# S603D.net
KiCad netlist of a schematic drawn in EAGLE
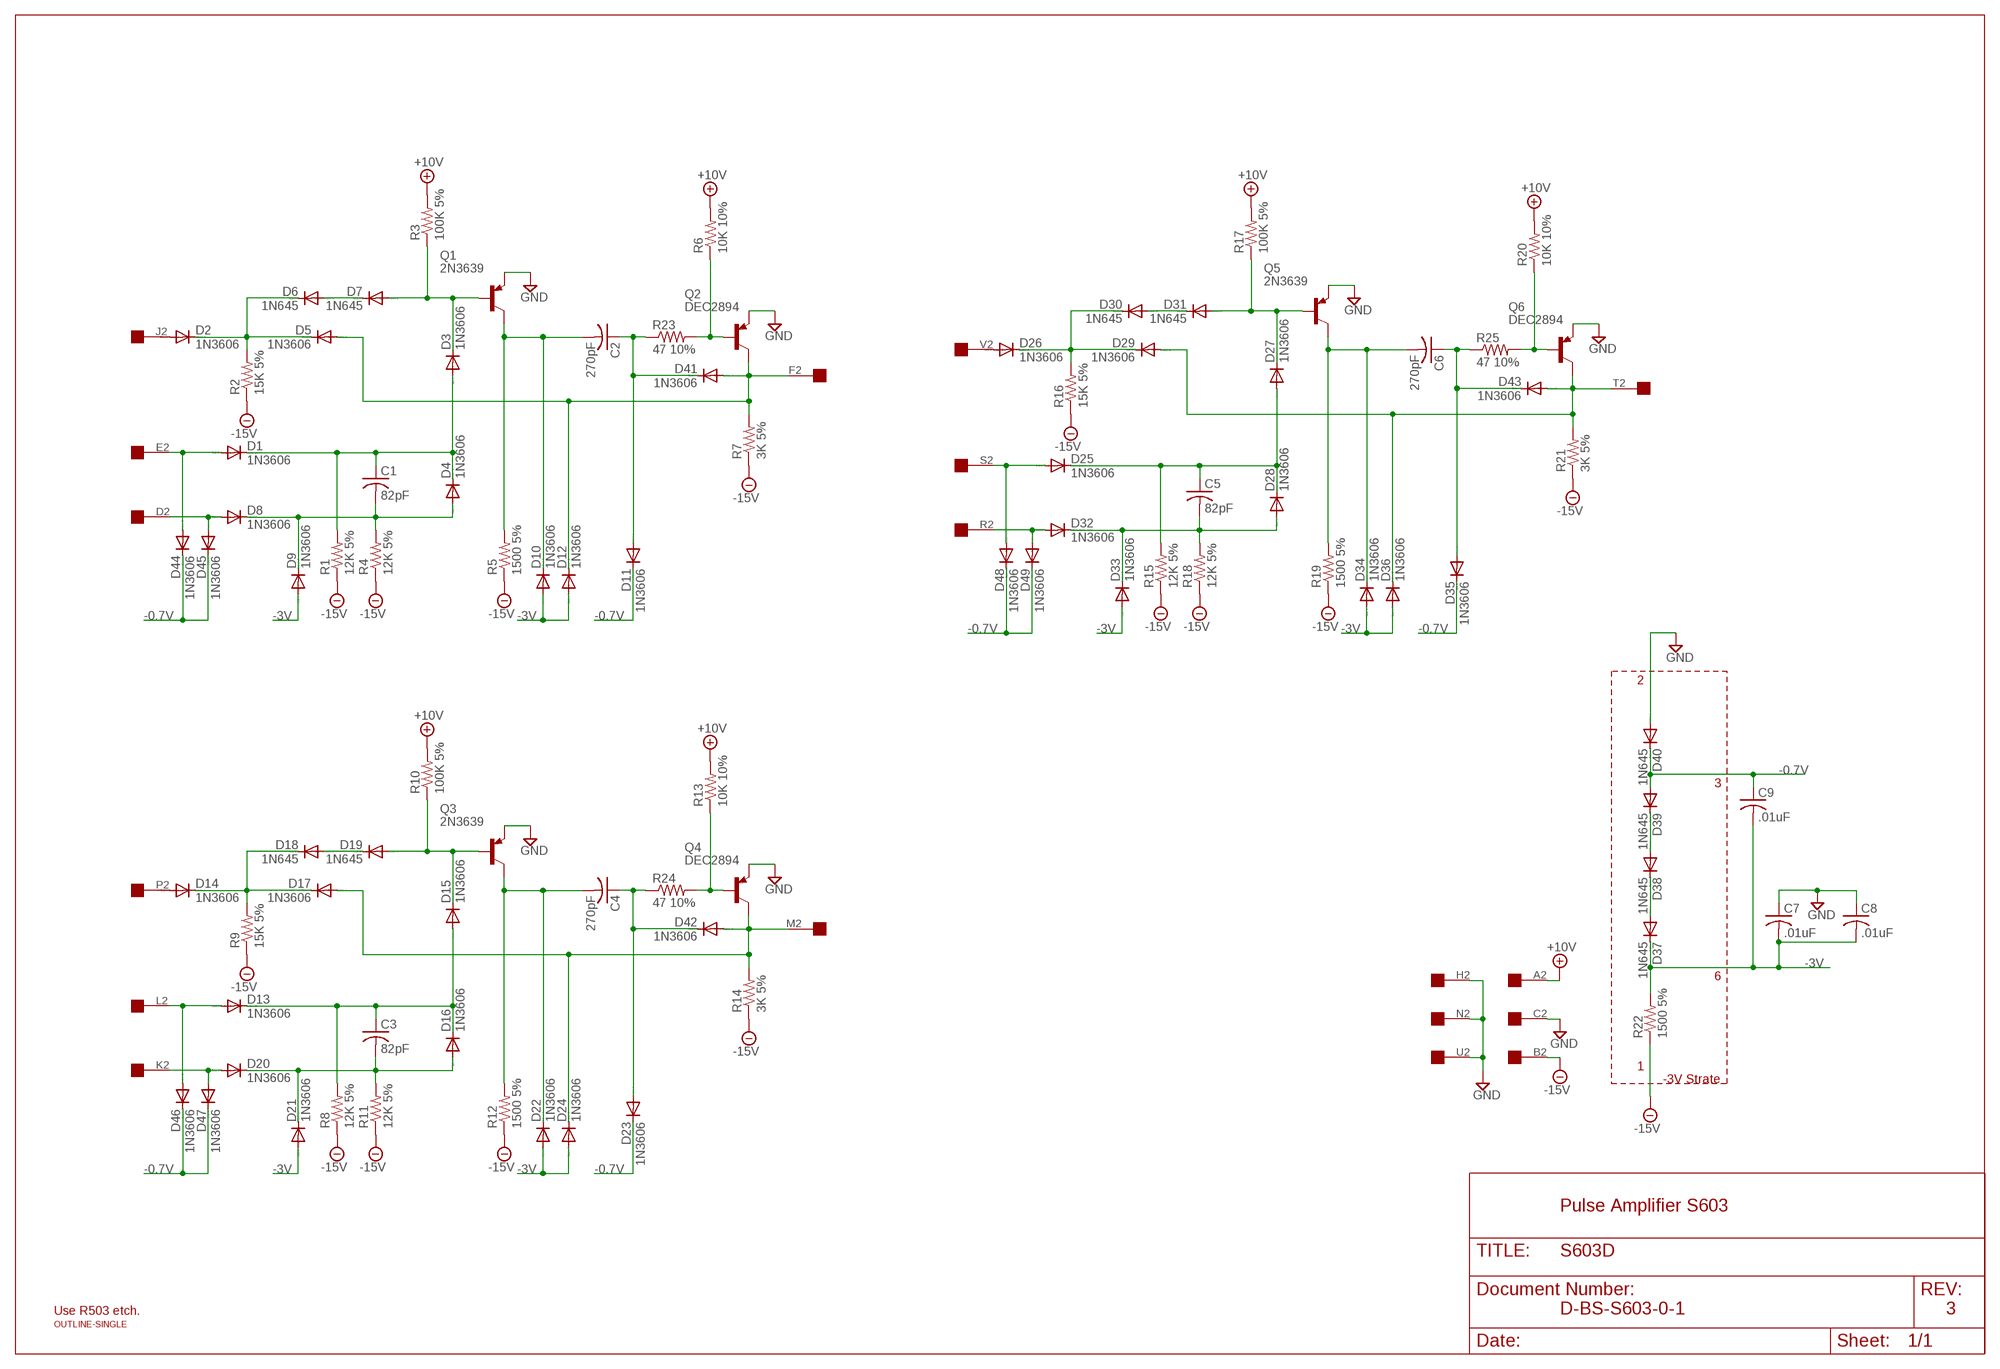
[diagram p0: schematic, sheet 1]

(export (version "E")
  (design (tool "Eeschema 10.0.6"))
  (components
    (comp (ref "C1")
      (value "82pF")
      (footprint "eagle-import:C050-025X075")
      (libsource (lib "eagle-import") (part "C-US050-025X075"))
    )
    (comp (ref "C2")
      (value "270pF")
      (footprint "eagle-import:C050-025X075")
      (libsource (lib "eagle-import") (part "C-US050-025X075"))
    )
    (comp (ref "C3")
      (value "82pF")
      (footprint "eagle-import:C050-025X075")
      (libsource (lib "eagle-import") (part "C-US050-025X075"))
    )
    (comp (ref "C4")
      (value "270pF")
      (footprint "eagle-import:C050-025X075")
      (libsource (lib "eagle-import") (part "C-US050-025X075"))
    )
    (comp (ref "C5")
      (value "82pF")
      (footprint "eagle-import:C050-025X075")
      (libsource (lib "eagle-import") (part "C-US050-025X075"))
    )
    (comp (ref "C6")
      (value "270pF")
      (footprint "eagle-import:C050-025X075")
      (libsource (lib "eagle-import") (part "C-US050-025X075"))
    )
    (comp (ref "C7")
      (value ".01uF")
      (footprint "eagle-import:C050-025X075")
      (libsource (lib "eagle-import") (part "C-US050-025X075"))
    )
    (comp (ref "C8")
      (value ".01uF")
      (footprint "eagle-import:C050-025X075")
      (libsource (lib "eagle-import") (part "C-US050-025X075"))
    )
    (comp (ref "C9")
      (value ".01uF")
      (footprint "eagle-import:C050-025X075")
      (libsource (lib "eagle-import") (part "C-US050-025X075"))
    )
    (comp (ref "D1")
      (value "1N3606")
      (footprint "eagle-import:DO35-10")
      (libsource (lib "eagle-import") (part "1N4148DO35-10"))
    )
    (comp (ref "D2")
      (value "1N3606")
      (footprint "eagle-import:DO35-10")
      (libsource (lib "eagle-import") (part "1N4148DO35-10"))
    )
    (comp (ref "D3")
      (value "1N3606")
      (footprint "eagle-import:DO35-10")
      (libsource (lib "eagle-import") (part "1N4148DO35-10"))
    )
    (comp (ref "D4")
      (value "1N3606")
      (footprint "eagle-import:DO35-10")
      (libsource (lib "eagle-import") (part "1N4148DO35-10"))
    )
    (comp (ref "D5")
      (value "1N3606")
      (footprint "eagle-import:DO35-10")
      (libsource (lib "eagle-import") (part "1N4148DO35-10"))
    )
    (comp (ref "D6")
      (value "1N645")
      (footprint "eagle-import:DO35-10")
      (libsource (lib "eagle-import") (part "1N4148DO35-10"))
    )
    (comp (ref "D7")
      (value "1N645")
      (footprint "eagle-import:DO35-10")
      (libsource (lib "eagle-import") (part "1N4148DO35-10"))
    )
    (comp (ref "D8")
      (value "1N3606")
      (footprint "eagle-import:DO35-10")
      (libsource (lib "eagle-import") (part "1N4148DO35-10"))
    )
    (comp (ref "D9")
      (value "1N3606")
      (footprint "eagle-import:DO35-10")
      (libsource (lib "eagle-import") (part "1N4148DO35-10"))
    )
    (comp (ref "D10")
      (value "1N3606")
      (footprint "eagle-import:DO35-10")
      (libsource (lib "eagle-import") (part "1N4148DO35-10"))
    )
    (comp (ref "D11")
      (value "1N3606")
      (footprint "eagle-import:DO35-10")
      (libsource (lib "eagle-import") (part "1N4148DO35-10"))
    )
    (comp (ref "D12")
      (value "1N3606")
      (footprint "eagle-import:DO35-10")
      (libsource (lib "eagle-import") (part "1N4148DO35-10"))
    )
    (comp (ref "D13")
      (value "1N3606")
      (footprint "eagle-import:DO35-10")
      (libsource (lib "eagle-import") (part "1N4148DO35-10"))
    )
    (comp (ref "D14")
      (value "1N3606")
      (footprint "eagle-import:DO35-10")
      (libsource (lib "eagle-import") (part "1N4148DO35-10"))
    )
    (comp (ref "D15")
      (value "1N3606")
      (footprint "eagle-import:DO35-10")
      (libsource (lib "eagle-import") (part "1N4148DO35-10"))
    )
    (comp (ref "D16")
      (value "1N3606")
      (footprint "eagle-import:DO35-10")
      (libsource (lib "eagle-import") (part "1N4148DO35-10"))
    )
    (comp (ref "D17")
      (value "1N3606")
      (footprint "eagle-import:DO35-10")
      (libsource (lib "eagle-import") (part "1N4148DO35-10"))
    )
    (comp (ref "D18")
      (value "1N645")
      (footprint "eagle-import:DO35-10")
      (libsource (lib "eagle-import") (part "1N4148DO35-10"))
    )
    (comp (ref "D19")
      (value "1N645")
      (footprint "eagle-import:DO35-10")
      (libsource (lib "eagle-import") (part "1N4148DO35-10"))
    )
    (comp (ref "D20")
      (value "1N3606")
      (footprint "eagle-import:DO35-10")
      (libsource (lib "eagle-import") (part "1N4148DO35-10"))
    )
    (comp (ref "D21")
      (value "1N3606")
      (footprint "eagle-import:DO35-10")
      (libsource (lib "eagle-import") (part "1N4148DO35-10"))
    )
    (comp (ref "D22")
      (value "1N3606")
      (footprint "eagle-import:DO35-10")
      (libsource (lib "eagle-import") (part "1N4148DO35-10"))
    )
    (comp (ref "D23")
      (value "1N3606")
      (footprint "eagle-import:DO35-10")
      (libsource (lib "eagle-import") (part "1N4148DO35-10"))
    )
    (comp (ref "D24")
      (value "1N3606")
      (footprint "eagle-import:DO35-10")
      (libsource (lib "eagle-import") (part "1N4148DO35-10"))
    )
    (comp (ref "D25")
      (value "1N3606")
      (footprint "eagle-import:DO35-10")
      (libsource (lib "eagle-import") (part "1N4148DO35-10"))
    )
    (comp (ref "D26")
      (value "1N3606")
      (footprint "eagle-import:DO35-10")
      (libsource (lib "eagle-import") (part "1N4148DO35-10"))
    )
    (comp (ref "D27")
      (value "1N3606")
      (footprint "eagle-import:DO35-10")
      (libsource (lib "eagle-import") (part "1N4148DO35-10"))
    )
    (comp (ref "D28")
      (value "1N3606")
      (footprint "eagle-import:DO35-10")
      (libsource (lib "eagle-import") (part "1N4148DO35-10"))
    )
    (comp (ref "D29")
      (value "1N3606")
      (footprint "eagle-import:DO35-10")
      (libsource (lib "eagle-import") (part "1N4148DO35-10"))
    )
    (comp (ref "D30")
      (value "1N645")
      (footprint "eagle-import:DO35-10")
      (libsource (lib "eagle-import") (part "1N4148DO35-10"))
    )
    (comp (ref "D31")
      (value "1N645")
      (footprint "eagle-import:DO35-10")
      (libsource (lib "eagle-import") (part "1N4148DO35-10"))
    )
    (comp (ref "D32")
      (value "1N3606")
      (footprint "eagle-import:DO35-10")
      (libsource (lib "eagle-import") (part "1N4148DO35-10"))
    )
    (comp (ref "D33")
      (value "1N3606")
      (footprint "eagle-import:DO35-10")
      (libsource (lib "eagle-import") (part "1N4148DO35-10"))
    )
    (comp (ref "D34")
      (value "1N3606")
      (footprint "eagle-import:DO35-10")
      (libsource (lib "eagle-import") (part "1N4148DO35-10"))
    )
    (comp (ref "D35")
      (value "1N3606")
      (footprint "eagle-import:DO35-10")
      (libsource (lib "eagle-import") (part "1N4148DO35-10"))
    )
    (comp (ref "D36")
      (value "1N3606")
      (footprint "eagle-import:DO35-10")
      (libsource (lib "eagle-import") (part "1N4148DO35-10"))
    )
    (comp (ref "D37")
      (value "1N645")
      (footprint "eagle-import:DO35-10")
      (libsource (lib "eagle-import") (part "1N4148DO35-10"))
    )
    (comp (ref "D38")
      (value "1N645")
      (footprint "eagle-import:DO35-10")
      (libsource (lib "eagle-import") (part "1N4148DO35-10"))
    )
    (comp (ref "D39")
      (value "1N645")
      (footprint "eagle-import:DO35-10")
      (libsource (lib "eagle-import") (part "1N4148DO35-10"))
    )
    (comp (ref "D40")
      (value "1N645")
      (footprint "eagle-import:DO35-10")
      (libsource (lib "eagle-import") (part "1N4148DO35-10"))
    )
    (comp (ref "D41")
      (value "1N3606")
      (footprint "eagle-import:DO35-10")
      (libsource (lib "eagle-import") (part "1N4148DO35-10"))
    )
    (comp (ref "D42")
      (value "1N3606")
      (footprint "eagle-import:DO35-10")
      (libsource (lib "eagle-import") (part "1N4148DO35-10"))
    )
    (comp (ref "D43")
      (value "1N3606")
      (footprint "eagle-import:DO35-10")
      (libsource (lib "eagle-import") (part "1N4148DO35-10"))
    )
    (comp (ref "D44")
      (value "1N3606")
      (footprint "eagle-import:DO35-10")
      (libsource (lib "eagle-import") (part "1N4148DO35-10"))
    )
    (comp (ref "D45")
      (value "1N3606")
      (footprint "eagle-import:DO35-10")
      (libsource (lib "eagle-import") (part "1N4148DO35-10"))
    )
    (comp (ref "D46")
      (value "1N3606")
      (footprint "eagle-import:DO35-10")
      (libsource (lib "eagle-import") (part "1N4148DO35-10"))
    )
    (comp (ref "D47")
      (value "1N3606")
      (footprint "eagle-import:DO35-10")
      (libsource (lib "eagle-import") (part "1N4148DO35-10"))
    )
    (comp (ref "D48")
      (value "1N3606")
      (footprint "eagle-import:DO35-10")
      (libsource (lib "eagle-import") (part "1N4148DO35-10"))
    )
    (comp (ref "D49")
      (value "1N3606")
      (footprint "eagle-import:DO35-10")
      (libsource (lib "eagle-import") (part "1N4148DO35-10"))
    )
    (comp (ref "Q1")
      (value "2N3639")
      (footprint "eagle-import:TO39")
      (libsource (lib "eagle-import") (part "2N2904"))
    )
    (comp (ref "Q2")
      (value "DEC2894")
      (footprint "eagle-import:TO39")
      (libsource (lib "eagle-import") (part "2N2904"))
    )
    (comp (ref "Q3")
      (value "2N3639")
      (footprint "eagle-import:TO39")
      (libsource (lib "eagle-import") (part "2N2904"))
    )
    (comp (ref "Q4")
      (value "DEC2894")
      (footprint "eagle-import:TO39")
      (libsource (lib "eagle-import") (part "2N2904"))
    )
    (comp (ref "Q5")
      (value "2N3639")
      (footprint "eagle-import:TO39")
      (libsource (lib "eagle-import") (part "2N2904"))
    )
    (comp (ref "Q6")
      (value "DEC2894")
      (footprint "eagle-import:TO39")
      (libsource (lib "eagle-import") (part "2N2904"))
    )
    (comp (ref "R1")
      (value "12K 5%")
      (footprint "eagle-import:0207_10")
      (libsource (lib "eagle-import") (part "R-US_0207/10"))
    )
    (comp (ref "R2")
      (value "15K 5%")
      (footprint "eagle-import:0207_10")
      (libsource (lib "eagle-import") (part "R-US_0207/10"))
    )
    (comp (ref "R3")
      (value "100K 5%")
      (footprint "eagle-import:0207_10")
      (libsource (lib "eagle-import") (part "R-US_0207/10"))
    )
    (comp (ref "R4")
      (value "12K 5%")
      (footprint "eagle-import:0207_10")
      (libsource (lib "eagle-import") (part "R-US_0207/10"))
    )
    (comp (ref "R5")
      (value "1500 5%")
      (footprint "eagle-import:0207_10")
      (libsource (lib "eagle-import") (part "R-US_0207/10"))
    )
    (comp (ref "R6")
      (value "10K 10%")
      (footprint "eagle-import:0207_10")
      (libsource (lib "eagle-import") (part "R-US_0207/10"))
    )
    (comp (ref "R7")
      (value "3K 5%")
      (footprint "eagle-import:0207_10")
      (libsource (lib "eagle-import") (part "R-US_0207/10"))
    )
    (comp (ref "R8")
      (value "12K 5%")
      (footprint "eagle-import:0207_10")
      (libsource (lib "eagle-import") (part "R-US_0207/10"))
    )
    (comp (ref "R9")
      (value "15K 5%")
      (footprint "eagle-import:0207_10")
      (libsource (lib "eagle-import") (part "R-US_0207/10"))
    )
    (comp (ref "R10")
      (value "100K 5%")
      (footprint "eagle-import:0207_10")
      (libsource (lib "eagle-import") (part "R-US_0207/10"))
    )
    (comp (ref "R11")
      (value "12K 5%")
      (footprint "eagle-import:0207_10")
      (libsource (lib "eagle-import") (part "R-US_0207/10"))
    )
    (comp (ref "R12")
      (value "1500 5%")
      (footprint "eagle-import:0207_10")
      (libsource (lib "eagle-import") (part "R-US_0207/10"))
    )
    (comp (ref "R13")
      (value "10K 10%")
      (footprint "eagle-import:0207_10")
      (libsource (lib "eagle-import") (part "R-US_0207/10"))
    )
    (comp (ref "R14")
      (value "3K 5%")
      (footprint "eagle-import:0207_10")
      (libsource (lib "eagle-import") (part "R-US_0207/10"))
    )
    (comp (ref "R15")
      (value "12K 5%")
      (footprint "eagle-import:0207_10")
      (libsource (lib "eagle-import") (part "R-US_0207/10"))
    )
    (comp (ref "R16")
      (value "15K 5%")
      (footprint "eagle-import:0207_10")
      (libsource (lib "eagle-import") (part "R-US_0207/10"))
    )
    (comp (ref "R17")
      (value "100K 5%")
      (footprint "eagle-import:0207_10")
      (libsource (lib "eagle-import") (part "R-US_0207/10"))
    )
    (comp (ref "R18")
      (value "12K 5%")
      (footprint "eagle-import:0207_10")
      (libsource (lib "eagle-import") (part "R-US_0207/10"))
    )
    (comp (ref "R19")
      (value "1500 5%")
      (footprint "eagle-import:0207_10")
      (libsource (lib "eagle-import") (part "R-US_0207/10"))
    )
    (comp (ref "R20")
      (value "10K 10%")
      (footprint "eagle-import:0207_10")
      (libsource (lib "eagle-import") (part "R-US_0207/10"))
    )
    (comp (ref "R21")
      (value "3K 5%")
      (footprint "eagle-import:0207_10")
      (libsource (lib "eagle-import") (part "R-US_0207/10"))
    )
    (comp (ref "R22")
      (value "1500 5%")
      (footprint "eagle-import:0207_10")
      (libsource (lib "eagle-import") (part "R-US_0207/10"))
    )
    (comp (ref "R23")
      (value "47 10%")
      (footprint "eagle-import:0207_10")
      (libsource (lib "eagle-import") (part "R-US_0207/10"))
    )
    (comp (ref "R24")
      (value "47 10%")
      (footprint "eagle-import:0207_10")
      (libsource (lib "eagle-import") (part "R-US_0207/10"))
    )
    (comp (ref "R25")
      (value "47 10%")
      (footprint "eagle-import:0207_10")
      (libsource (lib "eagle-import") (part "R-US_0207/10"))
    )
    (comp (ref "U$1")
      (value "OUTLINE-SINGLE")
      (footprint "eagle-import:SINGLE")
      (libsource (lib "eagle-import") (part "OUTLINE-SINGLE"))
    )
    (comp (ref "U$2")
      (value "EDGE-1")
      (footprint "eagle-import:EDGE-CON1")
      (libsource (lib "eagle-import") (part "EDGE-1"))
    )
  )
  (nets
    (net (code "1") (name "+10V") (class "Default")
      (node (ref "R10") (pin "2") (pinfunction "2_2") (pintype "passive"))
      (node (ref "R13") (pin "2") (pinfunction "2_2") (pintype "passive"))
      (node (ref "R17") (pin "2") (pinfunction "2_2") (pintype "passive"))
      (node (ref "R20") (pin "2") (pinfunction "2_2") (pintype "passive"))
      (node (ref "R3") (pin "2") (pinfunction "2_2") (pintype "passive"))
      (node (ref "R6") (pin "2") (pinfunction "2_2") (pintype "passive"))
      (node (ref "U$2") (pin "A2") (pinfunction "1_A2") (pintype "bidirectional"))
    )
    (net (code "2") (name "-15V") (class "Default")
      (node (ref "R1") (pin "1") (pinfunction "1_1") (pintype "passive"))
      (node (ref "R11") (pin "1") (pinfunction "1_1") (pintype "passive"))
      (node (ref "R12") (pin "1") (pinfunction "1_1") (pintype "passive"))
      (node (ref "R14") (pin "1") (pinfunction "1_1") (pintype "passive"))
      (node (ref "R15") (pin "1") (pinfunction "1_1") (pintype "passive"))
      (node (ref "R16") (pin "1") (pinfunction "1_1") (pintype "passive"))
      (node (ref "R18") (pin "1") (pinfunction "1_1") (pintype "passive"))
      (node (ref "R19") (pin "1") (pinfunction "1_1") (pintype "passive"))
      (node (ref "R2") (pin "1") (pinfunction "1_1") (pintype "passive"))
      (node (ref "R21") (pin "1") (pinfunction "1_1") (pintype "passive"))
      (node (ref "R22") (pin "1") (pinfunction "1_1") (pintype "passive"))
      (node (ref "R4") (pin "1") (pinfunction "1_1") (pintype "passive"))
      (node (ref "R5") (pin "1") (pinfunction "1_1") (pintype "passive"))
      (node (ref "R7") (pin "1") (pinfunction "1_1") (pintype "passive"))
      (node (ref "R8") (pin "1") (pinfunction "1_1") (pintype "passive"))
      (node (ref "R9") (pin "1") (pinfunction "1_1") (pintype "passive"))
      (node (ref "U$2") (pin "B2") (pinfunction "1_B2") (pintype "bidirectional"))
    )
    (net (code "3") (name "/-0.7V") (class "Default")
      (node (ref "C9") (pin "1") (pinfunction "1_1") (pintype "passive"))
      (node (ref "D11") (pin "C") (pinfunction "C_C") (pintype "passive"))
      (node (ref "D23") (pin "C") (pinfunction "C_C") (pintype "passive"))
      (node (ref "D35") (pin "C") (pinfunction "C_C") (pintype "passive"))
      (node (ref "D39") (pin "A") (pinfunction "A_A") (pintype "passive"))
      (node (ref "D40") (pin "C") (pinfunction "C_C") (pintype "passive"))
      (node (ref "D44") (pin "C") (pinfunction "C_C") (pintype "passive"))
      (node (ref "D45") (pin "C") (pinfunction "C_C") (pintype "passive"))
      (node (ref "D46") (pin "C") (pinfunction "C_C") (pintype "passive"))
      (node (ref "D47") (pin "C") (pinfunction "C_C") (pintype "passive"))
      (node (ref "D48") (pin "C") (pinfunction "C_C") (pintype "passive"))
      (node (ref "D49") (pin "C") (pinfunction "C_C") (pintype "passive"))
    )
    (net (code "4") (name "/-3V") (class "Default")
      (node (ref "C7") (pin "2") (pinfunction "2_2") (pintype "passive"))
      (node (ref "C8") (pin "2") (pinfunction "2_2") (pintype "passive"))
      (node (ref "C9") (pin "2") (pinfunction "2_2") (pintype "passive"))
      (node (ref "D10") (pin "A") (pinfunction "A_A") (pintype "passive"))
      (node (ref "D12") (pin "A") (pinfunction "A_A") (pintype "passive"))
      (node (ref "D21") (pin "A") (pinfunction "A_A") (pintype "passive"))
      (node (ref "D22") (pin "A") (pinfunction "A_A") (pintype "passive"))
      (node (ref "D24") (pin "A") (pinfunction "A_A") (pintype "passive"))
      (node (ref "D33") (pin "A") (pinfunction "A_A") (pintype "passive"))
      (node (ref "D34") (pin "A") (pinfunction "A_A") (pintype "passive"))
      (node (ref "D36") (pin "A") (pinfunction "A_A") (pintype "passive"))
      (node (ref "D37") (pin "C") (pinfunction "C_C") (pintype "passive"))
      (node (ref "D9") (pin "A") (pinfunction "A_A") (pintype "passive"))
      (node (ref "R22") (pin "2") (pinfunction "2_2") (pintype "passive"))
    )
    (net (code "5") (name "GND") (class "Default")
      (node (ref "C7") (pin "1") (pinfunction "1_1") (pintype "passive"))
      (node (ref "C8") (pin "1") (pinfunction "1_1") (pintype "passive"))
      (node (ref "D40") (pin "A") (pinfunction "A_A") (pintype "passive"))
      (node (ref "Q1") (pin "1") (pinfunction "E_1") (pintype "passive"))
      (node (ref "Q2") (pin "1") (pinfunction "E_1") (pintype "passive"))
      (node (ref "Q3") (pin "1") (pinfunction "E_1") (pintype "passive"))
      (node (ref "Q4") (pin "1") (pinfunction "E_1") (pintype "passive"))
      (node (ref "Q5") (pin "1") (pinfunction "E_1") (pintype "passive"))
      (node (ref "Q6") (pin "1") (pinfunction "E_1") (pintype "passive"))
      (node (ref "U$2") (pin "C2") (pinfunction "1_C2") (pintype "bidirectional"))
      (node (ref "U$2") (pin "H2") (pinfunction "1_H2") (pintype "bidirectional"))
      (node (ref "U$2") (pin "N2") (pinfunction "1_N2") (pintype "bidirectional"))
      (node (ref "U$2") (pin "U2") (pinfunction "1_U2") (pintype "bidirectional"))
    )
    (net (code "6") (name "Net-(C1-Pad1)") (class "Default")
      (node (ref "C1") (pin "1") (pinfunction "1_1") (pintype "passive"))
      (node (ref "D1") (pin "C") (pinfunction "C_C") (pintype "passive"))
      (node (ref "D3") (pin "A") (pinfunction "A_A") (pintype "passive"))
      (node (ref "D4") (pin "C") (pinfunction "C_C") (pintype "passive"))
      (node (ref "R1") (pin "2") (pinfunction "2_2") (pintype "passive"))
    )
    (net (code "7") (name "Net-(C1-Pad2)") (class "Default")
      (node (ref "C1") (pin "2") (pinfunction "2_2") (pintype "passive"))
      (node (ref "D4") (pin "A") (pinfunction "A_A") (pintype "passive"))
      (node (ref "D8") (pin "C") (pinfunction "C_C") (pintype "passive"))
      (node (ref "D9") (pin "C") (pinfunction "C_C") (pintype "passive"))
      (node (ref "R4") (pin "2") (pinfunction "2_2") (pintype "passive"))
    )
    (net (code "8") (name "Net-(C2-Pad1)") (class "Default")
      (node (ref "C2") (pin "1") (pinfunction "1_1") (pintype "passive"))
      (node (ref "D11") (pin "A") (pinfunction "A_A") (pintype "passive"))
      (node (ref "D41") (pin "C") (pinfunction "C_C") (pintype "passive"))
      (node (ref "R23") (pin "1") (pinfunction "1_1") (pintype "passive"))
    )
    (net (code "9") (name "Net-(C3-Pad1)") (class "Default")
      (node (ref "C3") (pin "1") (pinfunction "1_1") (pintype "passive"))
      (node (ref "D13") (pin "C") (pinfunction "C_C") (pintype "passive"))
      (node (ref "D15") (pin "A") (pinfunction "A_A") (pintype "passive"))
      (node (ref "D16") (pin "C") (pinfunction "C_C") (pintype "passive"))
      (node (ref "R8") (pin "2") (pinfunction "2_2") (pintype "passive"))
    )
    (net (code "10") (name "Net-(C3-Pad2)") (class "Default")
      (node (ref "C3") (pin "2") (pinfunction "2_2") (pintype "passive"))
      (node (ref "D16") (pin "A") (pinfunction "A_A") (pintype "passive"))
      (node (ref "D20") (pin "C") (pinfunction "C_C") (pintype "passive"))
      (node (ref "D21") (pin "C") (pinfunction "C_C") (pintype "passive"))
      (node (ref "R11") (pin "2") (pinfunction "2_2") (pintype "passive"))
    )
    (net (code "11") (name "Net-(C4-Pad1)") (class "Default")
      (node (ref "C4") (pin "1") (pinfunction "1_1") (pintype "passive"))
      (node (ref "D23") (pin "A") (pinfunction "A_A") (pintype "passive"))
      (node (ref "D42") (pin "C") (pinfunction "C_C") (pintype "passive"))
      (node (ref "R24") (pin "1") (pinfunction "1_1") (pintype "passive"))
    )
    (net (code "12") (name "Net-(C5-Pad1)") (class "Default")
      (node (ref "C5") (pin "1") (pinfunction "1_1") (pintype "passive"))
      (node (ref "D25") (pin "C") (pinfunction "C_C") (pintype "passive"))
      (node (ref "D27") (pin "A") (pinfunction "A_A") (pintype "passive"))
      (node (ref "D28") (pin "C") (pinfunction "C_C") (pintype "passive"))
      (node (ref "R15") (pin "2") (pinfunction "2_2") (pintype "passive"))
    )
    (net (code "13") (name "Net-(C5-Pad2)") (class "Default")
      (node (ref "C5") (pin "2") (pinfunction "2_2") (pintype "passive"))
      (node (ref "D28") (pin "A") (pinfunction "A_A") (pintype "passive"))
      (node (ref "D32") (pin "C") (pinfunction "C_C") (pintype "passive"))
      (node (ref "D33") (pin "C") (pinfunction "C_C") (pintype "passive"))
      (node (ref "R18") (pin "2") (pinfunction "2_2") (pintype "passive"))
    )
    (net (code "14") (name "Net-(C6-Pad1)") (class "Default")
      (node (ref "C6") (pin "1") (pinfunction "1_1") (pintype "passive"))
      (node (ref "D35") (pin "A") (pinfunction "A_A") (pintype "passive"))
      (node (ref "D43") (pin "C") (pinfunction "C_C") (pintype "passive"))
      (node (ref "R25") (pin "1") (pinfunction "1_1") (pintype "passive"))
    )
    (net (code "15") (name "Net-(D2-PadC)") (class "Default")
      (node (ref "D2") (pin "C") (pinfunction "C_C") (pintype "passive"))
      (node (ref "D5") (pin "C") (pinfunction "C_C") (pintype "passive"))
      (node (ref "D6") (pin "C") (pinfunction "C_C") (pintype "passive"))
      (node (ref "R2") (pin "2") (pinfunction "2_2") (pintype "passive"))
    )
    (net (code "16") (name "Net-(D6-PadA)") (class "Default")
      (node (ref "D6") (pin "A") (pinfunction "A_A") (pintype "passive"))
      (node (ref "D7") (pin "C") (pinfunction "C_C") (pintype "passive"))
    )
    (net (code "17") (name "Net-(D14-PadC)") (class "Default")
      (node (ref "D14") (pin "C") (pinfunction "C_C") (pintype "passive"))
      (node (ref "D17") (pin "C") (pinfunction "C_C") (pintype "passive"))
      (node (ref "D18") (pin "C") (pinfunction "C_C") (pintype "passive"))
      (node (ref "R9") (pin "2") (pinfunction "2_2") (pintype "passive"))
    )
    (net (code "18") (name "Net-(D18-PadA)") (class "Default")
      (node (ref "D18") (pin "A") (pinfunction "A_A") (pintype "passive"))
      (node (ref "D19") (pin "C") (pinfunction "C_C") (pintype "passive"))
    )
    (net (code "19") (name "Net-(D26-PadC)") (class "Default")
      (node (ref "D26") (pin "C") (pinfunction "C_C") (pintype "passive"))
      (node (ref "D29") (pin "C") (pinfunction "C_C") (pintype "passive"))
      (node (ref "D30") (pin "C") (pinfunction "C_C") (pintype "passive"))
      (node (ref "R16") (pin "2") (pinfunction "2_2") (pintype "passive"))
    )
    (net (code "20") (name "Net-(D30-PadA)") (class "Default")
      (node (ref "D30") (pin "A") (pinfunction "A_A") (pintype "passive"))
      (node (ref "D31") (pin "C") (pinfunction "C_C") (pintype "passive"))
    )
    (net (code "21") (name "Net-(D37-PadA)") (class "Default")
      (node (ref "D37") (pin "A") (pinfunction "A_A") (pintype "passive"))
      (node (ref "D38") (pin "C") (pinfunction "C_C") (pintype "passive"))
    )
    (net (code "22") (name "Net-(D38-PadA)") (class "Default")
      (node (ref "D38") (pin "A") (pinfunction "A_A") (pintype "passive"))
      (node (ref "D39") (pin "C") (pinfunction "C_C") (pintype "passive"))
    )
    (net (code "23") (name "Net-(Q1-B)") (class "Default")
      (node (ref "D3") (pin "C") (pinfunction "C_C") (pintype "passive"))
      (node (ref "D7") (pin "A") (pinfunction "A_A") (pintype "passive"))
      (node (ref "Q1") (pin "2") (pinfunction "B_2") (pintype "passive"))
      (node (ref "R3") (pin "1") (pinfunction "1_1") (pintype "passive"))
    )
    (net (code "24") (name "Net-(Q1-C)") (class "Default")
      (node (ref "C2") (pin "2") (pinfunction "2_2") (pintype "passive"))
      (node (ref "D10") (pin "C") (pinfunction "C_C") (pintype "passive"))
      (node (ref "Q1") (pin "3") (pinfunction "C_3") (pintype "passive"))
      (node (ref "R5") (pin "2") (pinfunction "2_2") (pintype "passive"))
    )
    (net (code "25") (name "Net-(Q2-B)") (class "Default")
      (node (ref "Q2") (pin "2") (pinfunction "B_2") (pintype "passive"))
      (node (ref "R23") (pin "2") (pinfunction "2_2") (pintype "passive"))
      (node (ref "R6") (pin "1") (pinfunction "1_1") (pintype "passive"))
    )
    (net (code "26") (name "Net-(Q2-C)") (class "Default")
      (node (ref "D12") (pin "C") (pinfunction "C_C") (pintype "passive"))
      (node (ref "D41") (pin "A") (pinfunction "A_A") (pintype "passive"))
      (node (ref "D5") (pin "A") (pinfunction "A_A") (pintype "passive"))
      (node (ref "Q2") (pin "3") (pinfunction "C_3") (pintype "passive"))
      (node (ref "R7") (pin "2") (pinfunction "2_2") (pintype "passive"))
      (node (ref "U$2") (pin "F2") (pinfunction "1_F2") (pintype "bidirectional"))
    )
    (net (code "27") (name "Net-(Q3-B)") (class "Default")
      (node (ref "D15") (pin "C") (pinfunction "C_C") (pintype "passive"))
      (node (ref "D19") (pin "A") (pinfunction "A_A") (pintype "passive"))
      (node (ref "Q3") (pin "2") (pinfunction "B_2") (pintype "passive"))
      (node (ref "R10") (pin "1") (pinfunction "1_1") (pintype "passive"))
    )
    (net (code "28") (name "Net-(Q3-C)") (class "Default")
      (node (ref "C4") (pin "2") (pinfunction "2_2") (pintype "passive"))
      (node (ref "D22") (pin "C") (pinfunction "C_C") (pintype "passive"))
      (node (ref "Q3") (pin "3") (pinfunction "C_3") (pintype "passive"))
      (node (ref "R12") (pin "2") (pinfunction "2_2") (pintype "passive"))
    )
    (net (code "29") (name "Net-(Q4-B)") (class "Default")
      (node (ref "Q4") (pin "2") (pinfunction "B_2") (pintype "passive"))
      (node (ref "R13") (pin "1") (pinfunction "1_1") (pintype "passive"))
      (node (ref "R24") (pin "2") (pinfunction "2_2") (pintype "passive"))
    )
    (net (code "30") (name "Net-(Q4-C)") (class "Default")
      (node (ref "D17") (pin "A") (pinfunction "A_A") (pintype "passive"))
      (node (ref "D24") (pin "C") (pinfunction "C_C") (pintype "passive"))
      (node (ref "D42") (pin "A") (pinfunction "A_A") (pintype "passive"))
      (node (ref "Q4") (pin "3") (pinfunction "C_3") (pintype "passive"))
      (node (ref "R14") (pin "2") (pinfunction "2_2") (pintype "passive"))
      (node (ref "U$2") (pin "M2") (pinfunction "1_M2") (pintype "bidirectional"))
    )
    (net (code "31") (name "Net-(Q5-B)") (class "Default")
      (node (ref "D27") (pin "C") (pinfunction "C_C") (pintype "passive"))
      (node (ref "D31") (pin "A") (pinfunction "A_A") (pintype "passive"))
      (node (ref "Q5") (pin "2") (pinfunction "B_2") (pintype "passive"))
      (node (ref "R17") (pin "1") (pinfunction "1_1") (pintype "passive"))
    )
    (net (code "32") (name "Net-(Q5-C)") (class "Default")
      (node (ref "C6") (pin "2") (pinfunction "2_2") (pintype "passive"))
      (node (ref "D34") (pin "C") (pinfunction "C_C") (pintype "passive"))
      (node (ref "Q5") (pin "3") (pinfunction "C_3") (pintype "passive"))
      (node (ref "R19") (pin "2") (pinfunction "2_2") (pintype "passive"))
    )
    (net (code "33") (name "Net-(Q6-B)") (class "Default")
      (node (ref "Q6") (pin "2") (pinfunction "B_2") (pintype "passive"))
      (node (ref "R20") (pin "1") (pinfunction "1_1") (pintype "passive"))
      (node (ref "R25") (pin "2") (pinfunction "2_2") (pintype "passive"))
    )
    (net (code "34") (name "Net-(Q6-C)") (class "Default")
      (node (ref "D29") (pin "A") (pinfunction "A_A") (pintype "passive"))
      (node (ref "D36") (pin "C") (pinfunction "C_C") (pintype "passive"))
      (node (ref "D43") (pin "A") (pinfunction "A_A") (pintype "passive"))
      (node (ref "Q6") (pin "3") (pinfunction "C_3") (pintype "passive"))
      (node (ref "R21") (pin "2") (pinfunction "2_2") (pintype "passive"))
      (node (ref "U$2") (pin "T2") (pinfunction "1_T2") (pintype "bidirectional"))
    )
    (net (code "35") (name "Net-(U$2D-1)") (class "Default")
      (node (ref "D45") (pin "A") (pinfunction "A_A") (pintype "passive"))
      (node (ref "D8") (pin "A") (pinfunction "A_A") (pintype "passive"))
      (node (ref "U$2") (pin "D2") (pinfunction "1_D2") (pintype "bidirectional"))
    )
    (net (code "36") (name "Net-(U$2E-1)") (class "Default")
      (node (ref "D1") (pin "A") (pinfunction "A_A") (pintype "passive"))
      (node (ref "D44") (pin "A") (pinfunction "A_A") (pintype "passive"))
      (node (ref "U$2") (pin "E2") (pinfunction "1_E2") (pintype "bidirectional"))
    )
    (net (code "37") (name "Net-(U$2H-1)") (class "Default")
      (node (ref "D2") (pin "A") (pinfunction "A_A") (pintype "passive"))
      (node (ref "U$2") (pin "J2") (pinfunction "1_J2") (pintype "bidirectional"))
    )
    (net (code "38") (name "Net-(U$2I-1)") (class "Default")
      (node (ref "D20") (pin "A") (pinfunction "A_A") (pintype "passive"))
      (node (ref "D47") (pin "A") (pinfunction "A_A") (pintype "passive"))
      (node (ref "U$2") (pin "K2") (pinfunction "1_K2") (pintype "bidirectional"))
    )
    (net (code "39") (name "Net-(U$2J-1)") (class "Default")
      (node (ref "D13") (pin "A") (pinfunction "A_A") (pintype "passive"))
      (node (ref "D46") (pin "A") (pinfunction "A_A") (pintype "passive"))
      (node (ref "U$2") (pin "L2") (pinfunction "1_L2") (pintype "bidirectional"))
    )
    (net (code "40") (name "Net-(U$2M-1)") (class "Default")
      (node (ref "D14") (pin "A") (pinfunction "A_A") (pintype "passive"))
      (node (ref "U$2") (pin "P2") (pinfunction "1_P2") (pintype "bidirectional"))
    )
    (net (code "41") (name "Net-(U$2N-1)") (class "Default")
      (node (ref "D32") (pin "A") (pinfunction "A_A") (pintype "passive"))
      (node (ref "D49") (pin "A") (pinfunction "A_A") (pintype "passive"))
      (node (ref "U$2") (pin "R2") (pinfunction "1_R2") (pintype "bidirectional"))
    )
    (net (code "42") (name "Net-(U$2O-1)") (class "Default")
      (node (ref "D25") (pin "A") (pinfunction "A_A") (pintype "passive"))
      (node (ref "D48") (pin "A") (pinfunction "A_A") (pintype "passive"))
      (node (ref "U$2") (pin "S2") (pinfunction "1_S2") (pintype "bidirectional"))
    )
    (net (code "43") (name "Net-(U$2R-1)") (class "Default")
      (node (ref "D26") (pin "A") (pinfunction "A_A") (pintype "passive"))
      (node (ref "U$2") (pin "V2") (pinfunction "1_V2") (pintype "bidirectional"))
    )
  )
)
